# ATMEGA.net
KiCad netlist of a schematic drawn in EAGLE
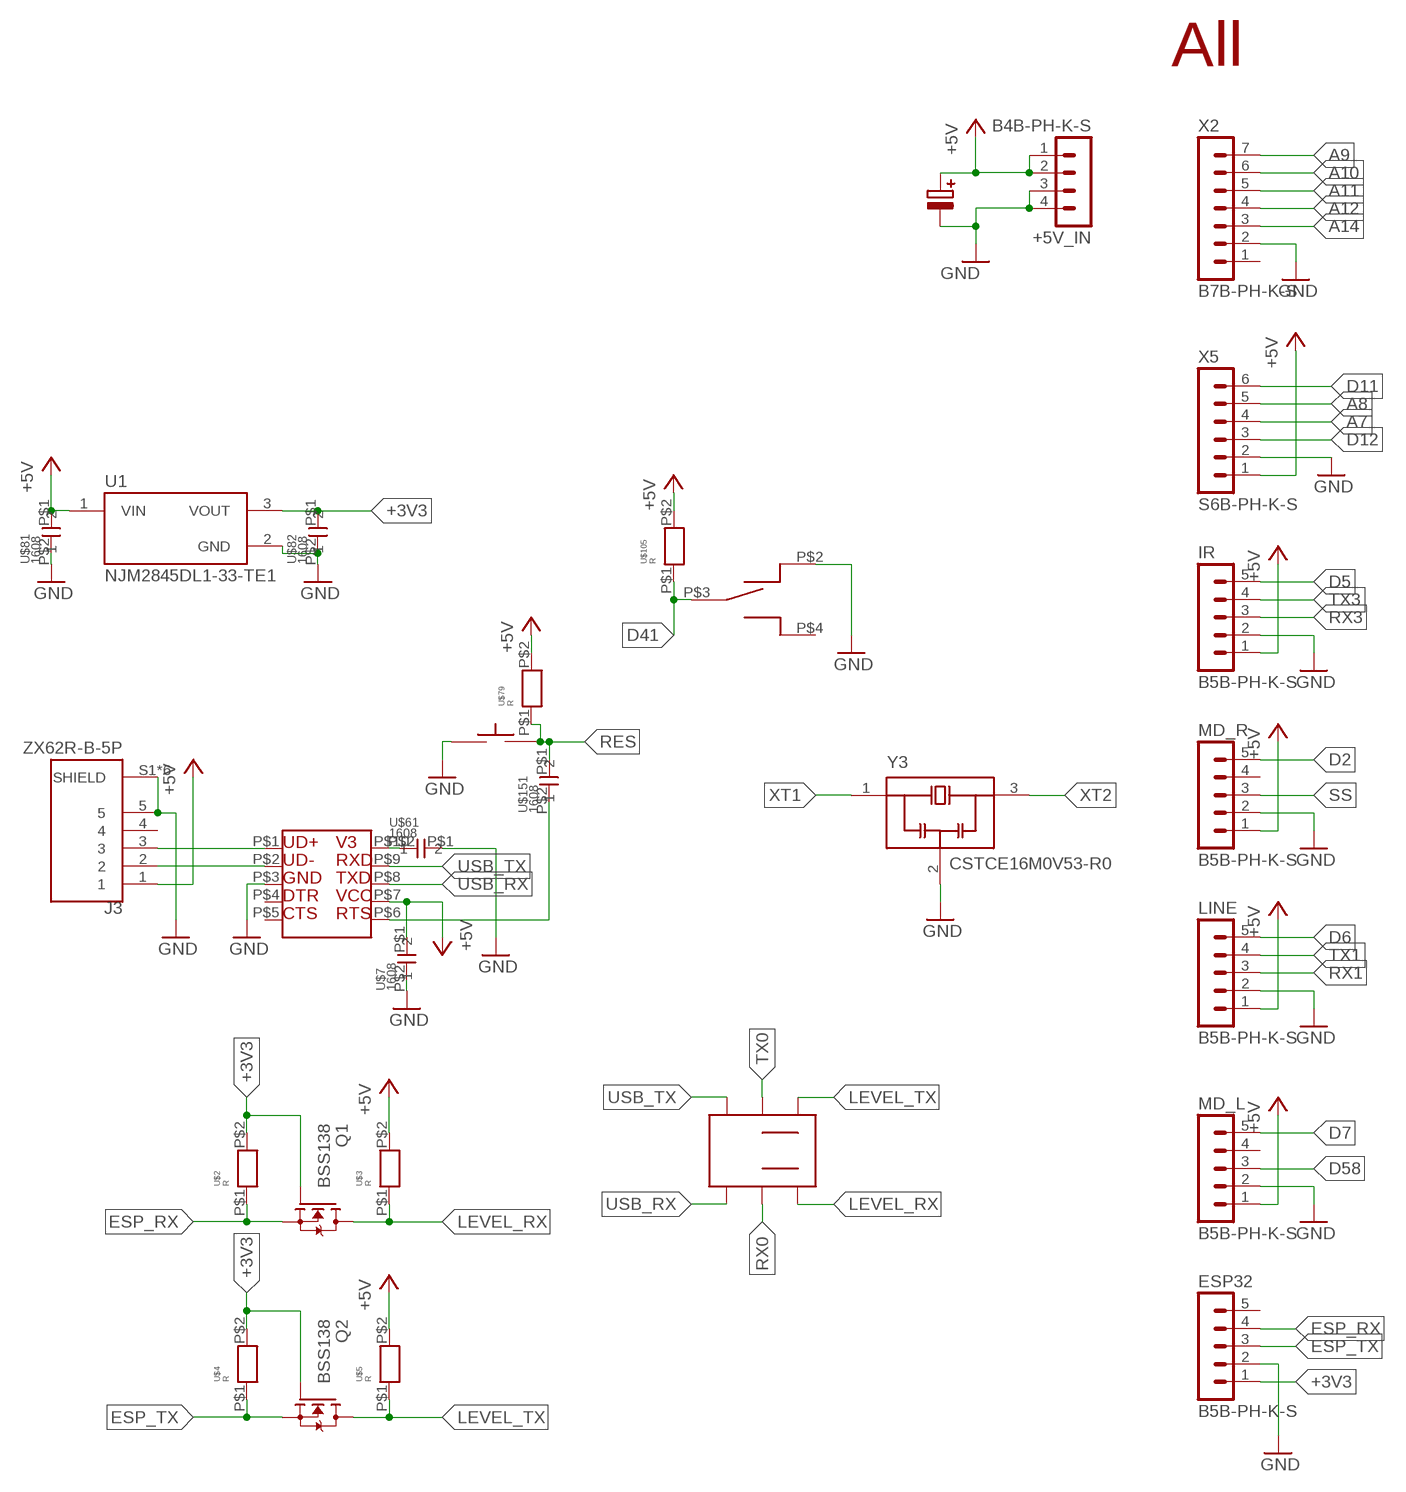
[diagram p0: schematic, sheet 1, part 1 of 2]
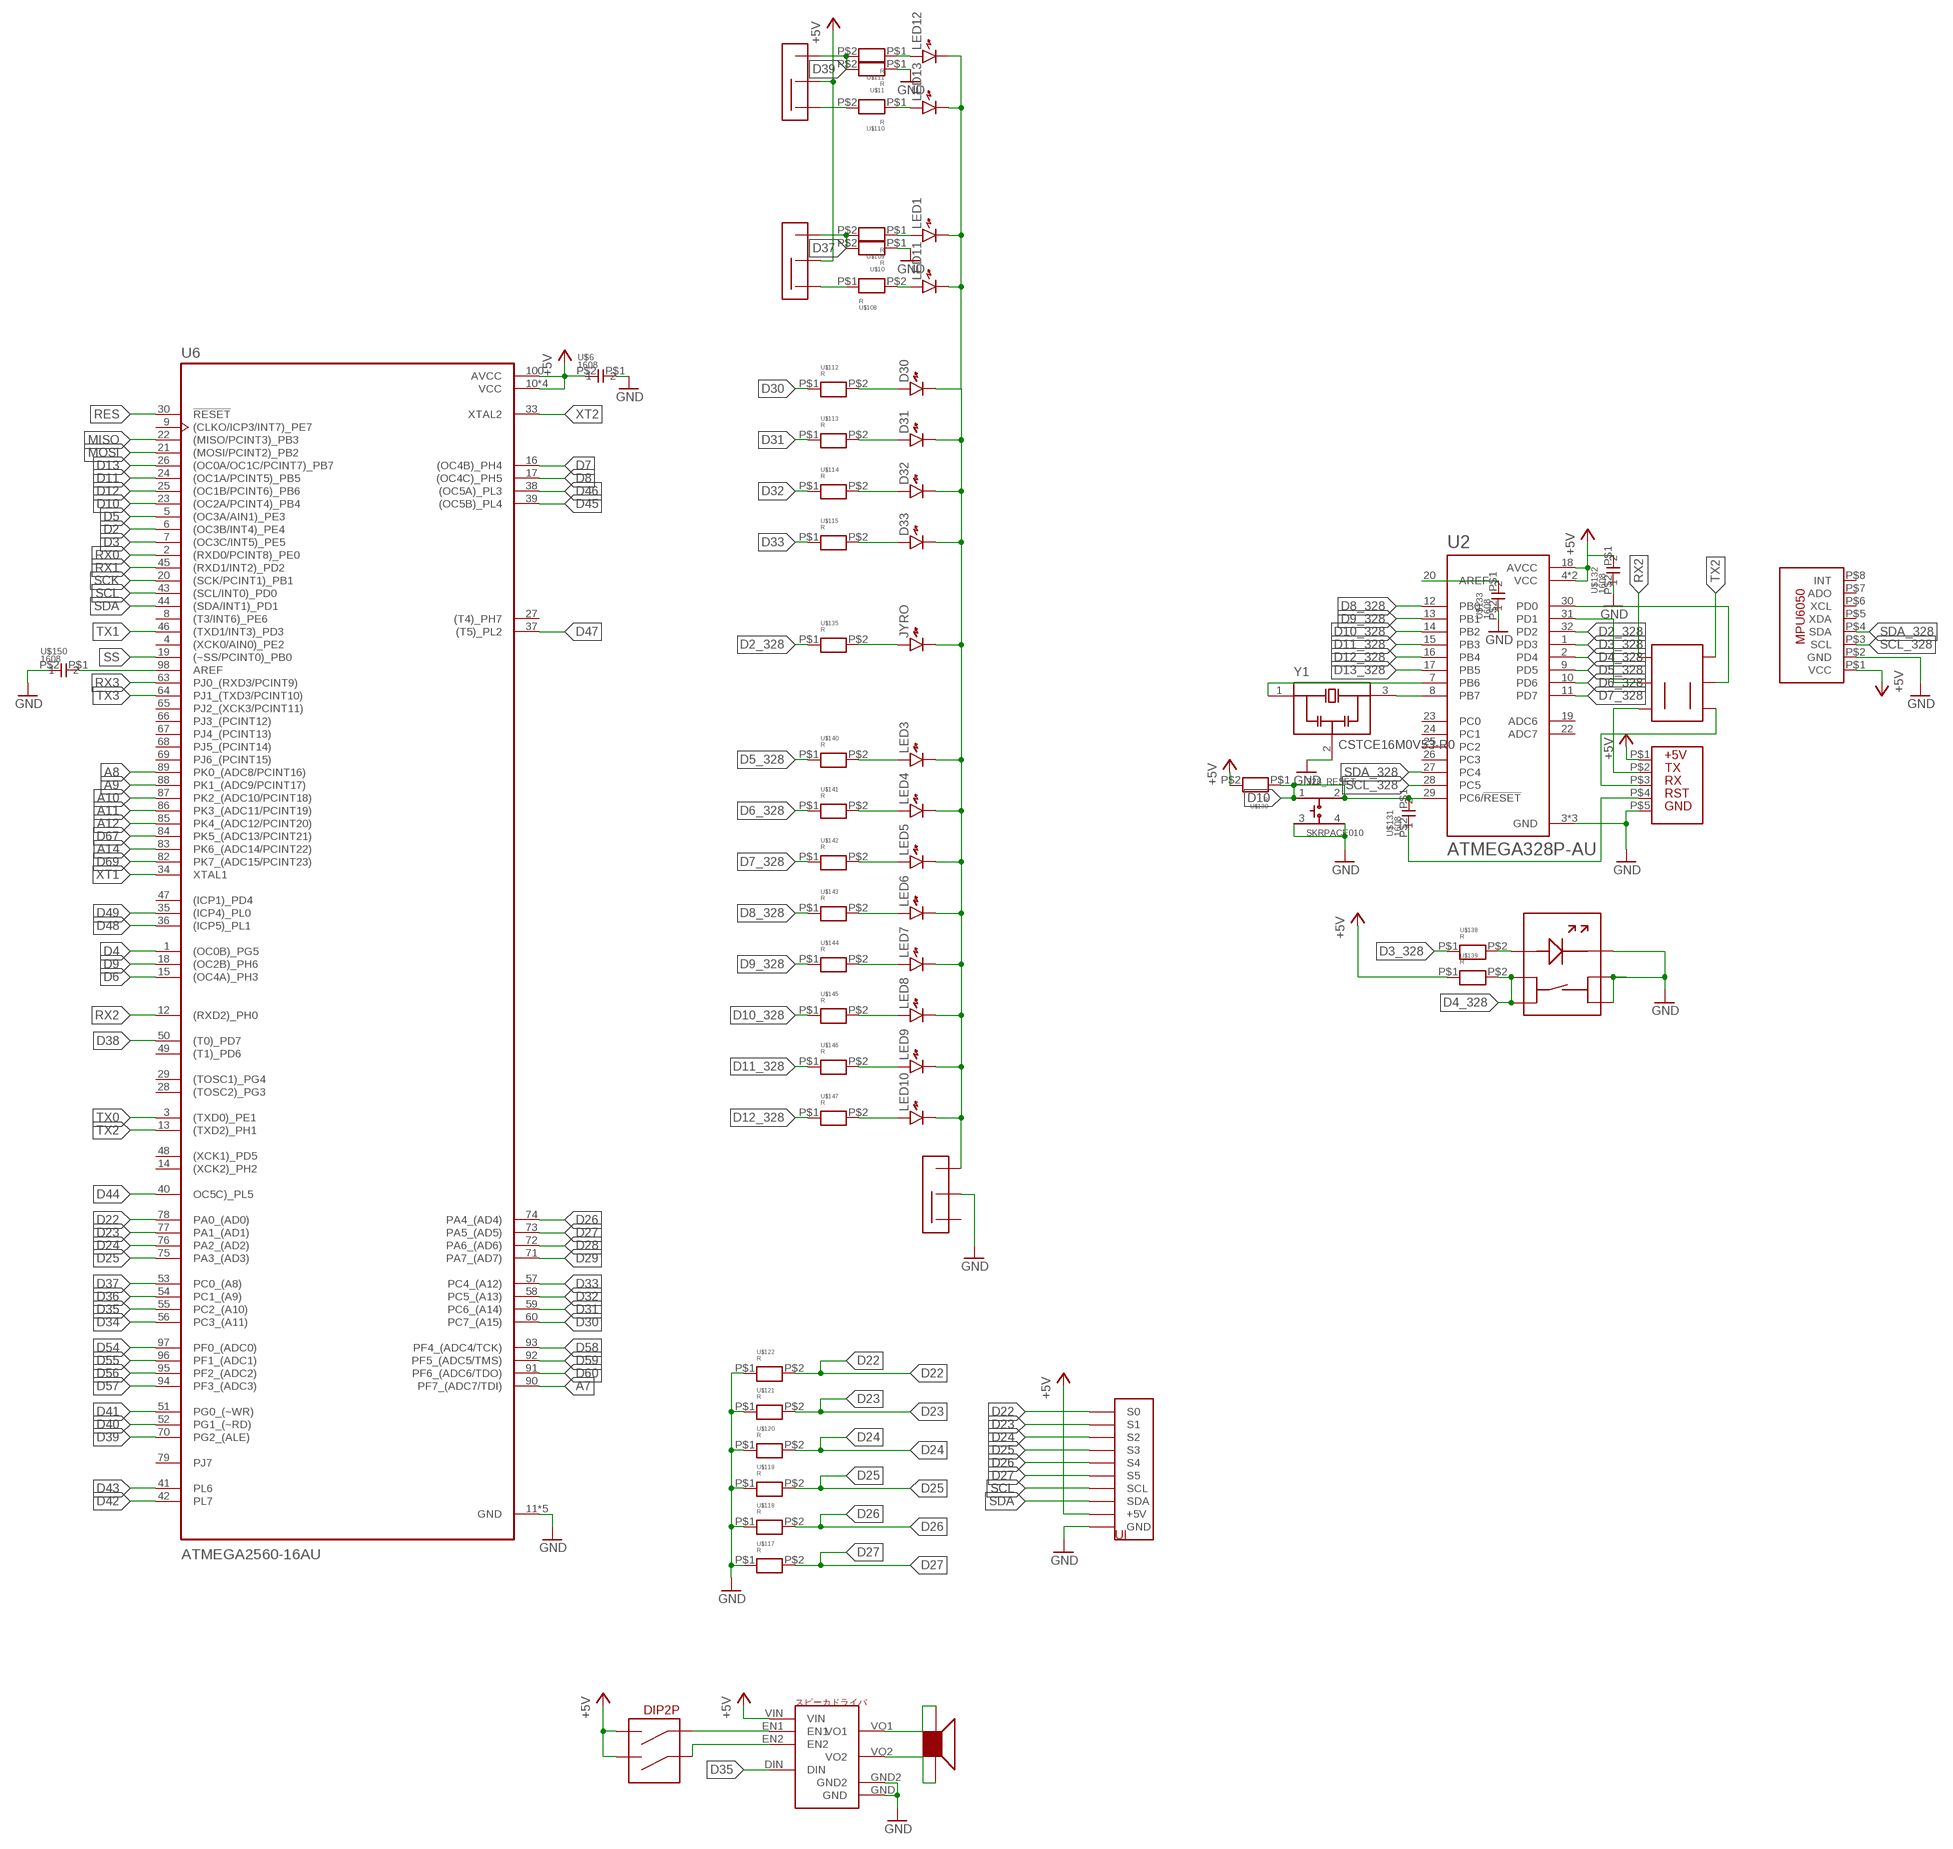
[diagram p1: schematic, sheet 1, part 2 of 2]

(export (version "E")
  (design (tool "Eeschema 10.0.6"))
  (components
    (comp (ref "+5V_IN")
      (value "B4B-PH-K-S")
      (footprint "eagle-import:B4B-PH-K-S")
      (libsource (lib "eagle-import") (part "B4B-PH-K-S"))
    )
    (comp (ref "328_RESET")
      (value "SKRPACE010")
      (footprint "eagle-import:SW_SKRPACE010")
      (fields (field (name "MF") "ALPS"))
      (libsource (lib "eagle-import") (part "SKRPACE010"))
    )
    (comp (ref "D30")
      (value "LED1608")
      (footprint "eagle-import:LED1608")
      (libsource (lib "eagle-import") (part "LED1608"))
    )
    (comp (ref "D31")
      (value "LED1608")
      (footprint "eagle-import:LED1608")
      (libsource (lib "eagle-import") (part "LED1608"))
    )
    (comp (ref "D32")
      (value "LED1608")
      (footprint "eagle-import:LED1608")
      (libsource (lib "eagle-import") (part "LED1608"))
    )
    (comp (ref "D33")
      (value "LED1608")
      (footprint "eagle-import:LED1608")
      (libsource (lib "eagle-import") (part "LED1608"))
    )
    (comp (ref "ESP32")
      (value "B5B-PH-K-S")
      (footprint "eagle-import:B5B-PH-K-S")
      (libsource (lib "eagle-import") (part "B5B-PH-K-S"))
    )
    (comp (ref "IR")
      (value "B5B-PH-K-S")
      (footprint "eagle-import:B5B-PH-K-S")
      (libsource (lib "eagle-import") (part "B5B-PH-K-S"))
    )
    (comp (ref "J3")
      (value "ZX62R-B-5P")
      (footprint "eagle-import:HRS_ZX62R-B-5P")
      (fields (field (name "MF") "Hirose"))
      (libsource (lib "eagle-import") (part "ZX62R-B-5P"))
    )
    (comp (ref "JYRO")
      (value "LED1608")
      (footprint "eagle-import:LED1608")
      (libsource (lib "eagle-import") (part "LED1608"))
    )
    (comp (ref "LED1")
      (value "LED1608")
      (footprint "eagle-import:LED1608")
      (libsource (lib "eagle-import") (part "LED1608"))
    )
    (comp (ref "LED3")
      (value "LED1608")
      (footprint "eagle-import:LED1608")
      (libsource (lib "eagle-import") (part "LED1608"))
    )
    (comp (ref "LED4")
      (value "LED1608")
      (footprint "eagle-import:LED1608")
      (libsource (lib "eagle-import") (part "LED1608"))
    )
    (comp (ref "LED5")
      (value "LED1608")
      (footprint "eagle-import:LED1608")
      (libsource (lib "eagle-import") (part "LED1608"))
    )
    (comp (ref "LED6")
      (value "LED1608")
      (footprint "eagle-import:LED1608")
      (libsource (lib "eagle-import") (part "LED1608"))
    )
    (comp (ref "LED7")
      (value "LED1608")
      (footprint "eagle-import:LED1608")
      (libsource (lib "eagle-import") (part "LED1608"))
    )
    (comp (ref "LED8")
      (value "LED1608")
      (footprint "eagle-import:LED1608")
      (libsource (lib "eagle-import") (part "LED1608"))
    )
    (comp (ref "LED9")
      (value "LED1608")
      (footprint "eagle-import:LED1608")
      (libsource (lib "eagle-import") (part "LED1608"))
    )
    (comp (ref "LED10")
      (value "LED1608")
      (footprint "eagle-import:LED1608")
      (libsource (lib "eagle-import") (part "LED1608"))
    )
    (comp (ref "LED11")
      (value "LED1608")
      (footprint "eagle-import:LED1608")
      (libsource (lib "eagle-import") (part "LED1608"))
    )
    (comp (ref "LED12")
      (value "LED1608")
      (footprint "eagle-import:LED1608")
      (libsource (lib "eagle-import") (part "LED1608"))
    )
    (comp (ref "LED13")
      (value "LED1608")
      (footprint "eagle-import:LED1608")
      (libsource (lib "eagle-import") (part "LED1608"))
    )
    (comp (ref "LINE")
      (value "B5B-PH-K-S")
      (footprint "eagle-import:B5B-PH-K-S")
      (libsource (lib "eagle-import") (part "B5B-PH-K-S"))
    )
    (comp (ref "MD_L")
      (value "B5B-PH-K-S")
      (footprint "eagle-import:B5B-PH-K-S")
      (libsource (lib "eagle-import") (part "B5B-PH-K-S"))
    )
    (comp (ref "MD_R")
      (value "B5B-PH-K-S")
      (footprint "eagle-import:B5B-PH-K-S")
      (libsource (lib "eagle-import") (part "B5B-PH-K-S"))
    )
    (comp (ref "Q1")
      (value "BSS138")
      (footprint "eagle-import:SOT23")
      (fields (field (name "MF") "Fairchild"))
      (libsource (lib "eagle-import") (part "BSS138"))
    )
    (comp (ref "Q2")
      (value "BSS138")
      (footprint "eagle-import:SOT23")
      (fields (field (name "MF") "Fairchild"))
      (libsource (lib "eagle-import") (part "BSS138"))
    )
    (comp (ref "U$1")
      (value "25V100")
      (footprint "eagle-import:25V100")
      (libsource (lib "eagle-import") (part "25V100"))
    )
    (comp (ref "U$2") (value "R") (footprint "eagle-import:1608") (libsource (lib "eagle-import") (part "R")))
    (comp (ref "U$3") (value "R") (footprint "eagle-import:1608") (libsource (lib "eagle-import") (part "R")))
    (comp (ref "U$4") (value "R") (footprint "eagle-import:1608") (libsource (lib "eagle-import") (part "R")))
    (comp (ref "U$5") (value "R") (footprint "eagle-import:1608") (libsource (lib "eagle-import") (part "R")))
    (comp (ref "U$6")
      (value "1608")
      (footprint "eagle-import:CON")
      (libsource (lib "eagle-import") (part "1608"))
    )
    (comp (ref "U$7")
      (value "1608")
      (footprint "eagle-import:CON")
      (libsource (lib "eagle-import") (part "1608"))
    )
    (comp (ref "U$8")
      (value "2SW")
      (footprint "eagle-import:2SW")
      (libsource (lib "eagle-import") (part "2SW"))
    )
    (comp (ref "U$9") (value "S") (footprint "eagle-import:S") (libsource (lib "eagle-import") (part "S")))
    (comp (ref "U$10")
      (value "R")
      (footprint "eagle-import:1608")
      (libsource (lib "eagle-import") (part "R"))
    )
    (comp (ref "U$11")
      (value "R")
      (footprint "eagle-import:1608")
      (libsource (lib "eagle-import") (part "R"))
    )
    (comp (ref "U$12")
      (value "BUZA-")
      (footprint "eagle-import:ぶざー")
      (libsource (lib "eagle-import") (part "BUZA-"))
    )
    (comp (ref "U$13")
      (value "BUZA_DR")
      (footprint "eagle-import:BUZA_DR")
      (libsource (lib "eagle-import") (part "BUZA_DR"))
    )
    (comp (ref "U$14")
      (value "DIP2")
      (footprint "eagle-import:DIP2")
      (libsource (lib "eagle-import") (part "DIP2"))
    )
    (comp (ref "U$46")
      (value "CH340K")
      (footprint "eagle-import:CH340K")
      (libsource (lib "eagle-import") (part "CH340K"))
    )
    (comp (ref "U$61")
      (value "1608")
      (footprint "eagle-import:CON")
      (libsource (lib "eagle-import") (part "1608"))
    )
    (comp (ref "U$79")
      (value "R")
      (footprint "eagle-import:1608")
      (libsource (lib "eagle-import") (part "R"))
    )
    (comp (ref "U$80")
      (value "TAKUTO")
      (footprint "eagle-import:12")
      (libsource (lib "eagle-import") (part "TAKUTO"))
    )
    (comp (ref "U$81")
      (value "1608")
      (footprint "eagle-import:CON")
      (libsource (lib "eagle-import") (part "1608"))
    )
    (comp (ref "U$82")
      (value "1608")
      (footprint "eagle-import:CON")
      (libsource (lib "eagle-import") (part "1608"))
    )
    (comp (ref "U$93")
      (value "ジャイロ")
      (footprint "eagle-import:ジャイロ")
      (libsource (lib "eagle-import") (part "ジャイロ"))
    )
    (comp (ref "U$105")
      (value "R")
      (footprint "eagle-import:1608")
      (libsource (lib "eagle-import") (part "R"))
    )
    (comp (ref "U$106")
      (value "SSW")
      (footprint "eagle-import:SSW")
      (libsource (lib "eagle-import") (part "SSW"))
    )
    (comp (ref "U$107")
      (value "SSW")
      (footprint "eagle-import:SSW")
      (libsource (lib "eagle-import") (part "SSW"))
    )
    (comp (ref "U$108")
      (value "R")
      (footprint "eagle-import:1608")
      (libsource (lib "eagle-import") (part "R"))
    )
    (comp (ref "U$109")
      (value "R")
      (footprint "eagle-import:1608")
      (libsource (lib "eagle-import") (part "R"))
    )
    (comp (ref "U$110")
      (value "R")
      (footprint "eagle-import:1608")
      (libsource (lib "eagle-import") (part "R"))
    )
    (comp (ref "U$111")
      (value "R")
      (footprint "eagle-import:1608")
      (libsource (lib "eagle-import") (part "R"))
    )
    (comp (ref "U$112")
      (value "R")
      (footprint "eagle-import:1608")
      (libsource (lib "eagle-import") (part "R"))
    )
    (comp (ref "U$113")
      (value "R")
      (footprint "eagle-import:1608")
      (libsource (lib "eagle-import") (part "R"))
    )
    (comp (ref "U$114")
      (value "R")
      (footprint "eagle-import:1608")
      (libsource (lib "eagle-import") (part "R"))
    )
    (comp (ref "U$115")
      (value "R")
      (footprint "eagle-import:1608")
      (libsource (lib "eagle-import") (part "R"))
    )
    (comp (ref "U$117")
      (value "R")
      (footprint "eagle-import:1608")
      (libsource (lib "eagle-import") (part "R"))
    )
    (comp (ref "U$118")
      (value "R")
      (footprint "eagle-import:1608")
      (libsource (lib "eagle-import") (part "R"))
    )
    (comp (ref "U$119")
      (value "R")
      (footprint "eagle-import:1608")
      (libsource (lib "eagle-import") (part "R"))
    )
    (comp (ref "U$120")
      (value "R")
      (footprint "eagle-import:1608")
      (libsource (lib "eagle-import") (part "R"))
    )
    (comp (ref "U$121")
      (value "R")
      (footprint "eagle-import:1608")
      (libsource (lib "eagle-import") (part "R"))
    )
    (comp (ref "U$122")
      (value "R")
      (footprint "eagle-import:1608")
      (libsource (lib "eagle-import") (part "R"))
    )
    (comp (ref "U$130")
      (value "R")
      (footprint "eagle-import:1608")
      (libsource (lib "eagle-import") (part "R"))
    )
    (comp (ref "U$131")
      (value "1608")
      (footprint "eagle-import:CON")
      (libsource (lib "eagle-import") (part "1608"))
    )
    (comp (ref "U$132")
      (value "1608")
      (footprint "eagle-import:CON")
      (libsource (lib "eagle-import") (part "1608"))
    )
    (comp (ref "U$133")
      (value "1608")
      (footprint "eagle-import:CON")
      (libsource (lib "eagle-import") (part "1608"))
    )
    (comp (ref "U$134")
      (value "SI")
      (footprint "eagle-import:SI")
      (libsource (lib "eagle-import") (part "SI"))
    )
    (comp (ref "U$135")
      (value "R")
      (footprint "eagle-import:1608")
      (libsource (lib "eagle-import") (part "R"))
    )
    (comp (ref "U$136")
      (value "2SW")
      (footprint "eagle-import:2SW")
      (libsource (lib "eagle-import") (part "2SW"))
    )
    (comp (ref "U$137")
      (value "SWLED")
      (footprint "eagle-import:SWLED")
      (libsource (lib "eagle-import") (part "SWLED"))
    )
    (comp (ref "U$138")
      (value "R")
      (footprint "eagle-import:1608")
      (libsource (lib "eagle-import") (part "R"))
    )
    (comp (ref "U$139")
      (value "R")
      (footprint "eagle-import:1608")
      (libsource (lib "eagle-import") (part "R"))
    )
    (comp (ref "U$140")
      (value "R")
      (footprint "eagle-import:1608")
      (libsource (lib "eagle-import") (part "R"))
    )
    (comp (ref "U$141")
      (value "R")
      (footprint "eagle-import:1608")
      (libsource (lib "eagle-import") (part "R"))
    )
    (comp (ref "U$142")
      (value "R")
      (footprint "eagle-import:1608")
      (libsource (lib "eagle-import") (part "R"))
    )
    (comp (ref "U$143")
      (value "R")
      (footprint "eagle-import:1608")
      (libsource (lib "eagle-import") (part "R"))
    )
    (comp (ref "U$144")
      (value "R")
      (footprint "eagle-import:1608")
      (libsource (lib "eagle-import") (part "R"))
    )
    (comp (ref "U$145")
      (value "R")
      (footprint "eagle-import:1608")
      (libsource (lib "eagle-import") (part "R"))
    )
    (comp (ref "U$146")
      (value "R")
      (footprint "eagle-import:1608")
      (libsource (lib "eagle-import") (part "R"))
    )
    (comp (ref "U$147")
      (value "R")
      (footprint "eagle-import:1608")
      (libsource (lib "eagle-import") (part "R"))
    )
    (comp (ref "U$148")
      (value "SSW")
      (footprint "eagle-import:SSW")
      (libsource (lib "eagle-import") (part "SSW"))
    )
    (comp (ref "U$149")
      (value "UI")
      (footprint "eagle-import:UI")
      (libsource (lib "eagle-import") (part "UI"))
    )
    (comp (ref "U$150")
      (value "1608")
      (footprint "eagle-import:CON")
      (libsource (lib "eagle-import") (part "1608"))
    )
    (comp (ref "U$151")
      (value "1608")
      (footprint "eagle-import:CON")
      (libsource (lib "eagle-import") (part "1608"))
    )
    (comp (ref "U$152")
      (value "ALL")
      (footprint "eagle-import:ALL")
      (libsource (lib "eagle-import") (part "ALL"))
    )
    (comp (ref "U1")
      (value "NJM2845DL1-33-TE1")
      (footprint "eagle-import:DPAK228P968X238-4N")
      (fields (field (name "MF") "NJR Corporation/NJRC"))
      (libsource (lib "eagle-import") (part "NJM2845DL1-33-TE1"))
    )
    (comp (ref "U2")
      (value "ATMEGA328P-AU")
      (footprint "eagle-import:QFP80P900X900X120-32N")
      (fields (field (name "MF") "Microchip Technology"))
      (libsource (lib "eagle-import") (part "ATMEGA328P-AU"))
    )
    (comp (ref "U6")
      (value "ATMEGA2560-16AU")
      (footprint "eagle-import:QFP50P1600X1600X120-100N")
      (fields (field (name "MF") "Microchip Technology"))
      (libsource (lib "eagle-import") (part "ATMEGA2560-16AU"))
    )
    (comp (ref "X2")
      (value "B7B-PH-K-S")
      (footprint "eagle-import:B7B-PH-K-S")
      (libsource (lib "eagle-import") (part "B7B-PH-K-S"))
    )
    (comp (ref "X5")
      (value "S6B-PH-K-S")
      (footprint "eagle-import:S6B-PH-K-S")
      (libsource (lib "eagle-import") (part "S6B-PH-K-S"))
    )
    (comp (ref "Y1")
      (value "CSTCE16M0V53-R0")
      (footprint "eagle-import:OSC_CSTCE16M0V53-R0")
      (fields (field (name "MANUFACTURER") "Murata"))
      (libsource (lib "eagle-import") (part "CSTCE16M0V53-R0"))
    )
    (comp (ref "Y3")
      (value "CSTCE16M0V53-R0")
      (footprint "eagle-import:OSC_CSTCE16M0V53-R0")
      (fields (field (name "MANUFACTURER") "Murata"))
      (libsource (lib "eagle-import") (part "CSTCE16M0V53-R0"))
    )
  )
  (nets
    (net (code "1") (name "+3V3") (class "Default")
      (node (ref "ESP32") (pin "1") (pinfunction "1_1") (pintype "passive"))
      (node (ref "Q1") (pin "1") (pinfunction "G_1") (pintype "passive"))
      (node (ref "Q2") (pin "1") (pinfunction "G_1") (pintype "passive"))
      (node (ref "U$2") (pin "P$2") (pinfunction "P$2_P$2") (pintype "bidirectional"))
      (node (ref "U$4") (pin "P$2") (pinfunction "P$2_P$2") (pintype "bidirectional"))
      (node (ref "U$82") (pin "P$1") (pinfunction "1_P$1") (pintype "bidirectional"))
      (node (ref "U1") (pin "3") (pinfunction "VOUT_3") (pintype "output"))
    )
    (net (code "2") (name "+5V") (class "Default")
      (node (ref "+5V_IN") (pin "1") (pinfunction "1_1") (pintype "passive"))
      (node (ref "+5V_IN") (pin "2") (pinfunction "2_2") (pintype "passive"))
      (node (ref "IR") (pin "1") (pinfunction "1_1") (pintype "passive"))
      (node (ref "J3") (pin "1") (pinfunction "1_1") (pintype "passive"))
      (node (ref "LINE") (pin "1") (pinfunction "1_1") (pintype "passive"))
      (node (ref "MD_L") (pin "1") (pinfunction "1_1") (pintype "passive"))
      (node (ref "MD_R") (pin "1") (pinfunction "1_1") (pintype "passive"))
      (node (ref "U$1") (pin "P$1") (pinfunction "P$1_P$1") (pintype "bidirectional"))
      (node (ref "U$105") (pin "P$2") (pinfunction "P$2_P$2") (pintype "bidirectional"))
      (node (ref "U$106") (pin "P$3") (pinfunction "P$2_P$3") (pintype "bidirectional"))
      (node (ref "U$107") (pin "P$3") (pinfunction "P$2_P$3") (pintype "bidirectional"))
      (node (ref "U$13") (pin "VIN") (pinfunction "VIN_VIN") (pintype "bidirectional"))
      (node (ref "U$130") (pin "P$2") (pinfunction "P$2_P$2") (pintype "bidirectional"))
      (node (ref "U$132") (pin "P$1") (pinfunction "1_P$1") (pintype "bidirectional"))
      (node (ref "U$134") (pin "P$1") (pinfunction "P$1_P$1") (pintype "bidirectional"))
      (node (ref "U$139") (pin "P$1") (pinfunction "P$1_P$1") (pintype "bidirectional"))
      (node (ref "U$14") (pin "P$15") (pinfunction "P$15_P$15") (pintype "bidirectional"))
      (node (ref "U$14") (pin "P$16") (pinfunction "P$16_P$16") (pintype "bidirectional"))
      (node (ref "U$149") (pin "P$1") (pinfunction "+5V_P$1") (pintype "bidirectional"))
      (node (ref "U$3") (pin "P$2") (pinfunction "P$2_P$2") (pintype "bidirectional"))
      (node (ref "U$46") (pin "P$7") (pinfunction "P$7_P$7") (pintype "bidirectional"))
      (node (ref "U$5") (pin "P$2") (pinfunction "P$2_P$2") (pintype "bidirectional"))
      (node (ref "U$6") (pin "P$2") (pinfunction "2_P$2") (pintype "bidirectional"))
      (node (ref "U$7") (pin "P$1") (pinfunction "1_P$1") (pintype "bidirectional"))
      (node (ref "U$79") (pin "P$2") (pinfunction "P$2_P$2") (pintype "bidirectional"))
      (node (ref "U$81") (pin "P$1") (pinfunction "1_P$1") (pintype "bidirectional"))
      (node (ref "U$93") (pin "P$1") (pinfunction "VCC_P$1") (pintype "bidirectional"))
      (node (ref "U1") (pin "1") (pinfunction "VIN_1") (pintype "input"))
      (node (ref "U2") (pin "18") (pinfunction "AVCC_18") (pintype "power_in"))
      (node (ref "U2") (pin "4") (pinfunction "VCC_4") (pintype "power_in"))
      (node (ref "U2") (pin "6") (pinfunction "VCC_6") (pintype "power_in"))
      (node (ref "U6") (pin "10") (pinfunction "VCC_10") (pintype "power_in"))
      (node (ref "U6") (pin "100") (pinfunction "AVCC_100") (pintype "power_in"))
      (node (ref "U6") (pin "31") (pinfunction "VCC_31") (pintype "power_in"))
      (node (ref "U6") (pin "61") (pinfunction "VCC_61") (pintype "power_in"))
      (node (ref "U6") (pin "80") (pinfunction "VCC_80") (pintype "power_in"))
      (node (ref "X5") (pin "1") (pinfunction "1_1") (pintype "passive"))
    )
    (net (code "3") (name "A7") (class "Default")
      (node (ref "U6") (pin "90") (pinfunction "PF7_(ADC7/TDI)_90") (pintype "bidirectional"))
      (node (ref "X5") (pin "4") (pinfunction "4_4") (pintype "passive"))
    )
    (net (code "4") (name "A8") (class "Default")
      (node (ref "U6") (pin "89") (pinfunction "PK0_(ADC8/PCINT16)_89") (pintype "input"))
      (node (ref "X5") (pin "5") (pinfunction "5_5") (pintype "passive"))
    )
    (net (code "5") (name "A9") (class "Default")
      (node (ref "U6") (pin "88") (pinfunction "PK1_(ADC9/PCINT17)_88") (pintype "input"))
      (node (ref "X2") (pin "7") (pinfunction "7_7") (pintype "passive"))
    )
    (net (code "6") (name "A10") (class "Default")
      (node (ref "U6") (pin "87") (pinfunction "PK2_(ADC10/PCINT18)_87") (pintype "input"))
      (node (ref "X2") (pin "6") (pinfunction "6_6") (pintype "passive"))
    )
    (net (code "7") (name "A11") (class "Default")
      (node (ref "U6") (pin "86") (pinfunction "PK3_(ADC11/PCINT19)_86") (pintype "input"))
      (node (ref "X2") (pin "5") (pinfunction "5_5") (pintype "passive"))
    )
    (net (code "8") (name "A12") (class "Default")
      (node (ref "U6") (pin "85") (pinfunction "PK4_(ADC12/PCINT20)_85") (pintype "input"))
      (node (ref "X2") (pin "4") (pinfunction "4_4") (pintype "passive"))
    )
    (net (code "9") (name "A14") (class "Default")
      (node (ref "U6") (pin "83") (pinfunction "PK6_(ADC14/PCINT22)_83") (pintype "input"))
      (node (ref "X2") (pin "3") (pinfunction "3_3") (pintype "passive"))
    )
    (net (code "10") (name "D2") (class "Default")
      (node (ref "MD_R") (pin "5") (pinfunction "5_5") (pintype "passive"))
      (node (ref "U6") (pin "6") (pinfunction "(OC3B/INT4)_PE4_6") (pintype "input"))
    )
    (net (code "11") (name "D2_328") (class "Default")
      (node (ref "U$135") (pin "P$1") (pinfunction "P$1_P$1") (pintype "bidirectional"))
      (node (ref "U2") (pin "32") (pinfunction "PD2_32") (pintype "bidirectional"))
    )
    (net (code "12") (name "D3") (class "Default")
      (node (ref "U6") (pin "7") (pinfunction "(OC3C/INT5)_PE5_7") (pintype "input"))
    )
    (net (code "13") (name "D3_328") (class "Default")
      (node (ref "U$138") (pin "P$1") (pinfunction "P$1_P$1") (pintype "bidirectional"))
      (node (ref "U2") (pin "1") (pinfunction "PD3_1") (pintype "bidirectional"))
    )
    (net (code "14") (name "D4") (class "Default")
      (node (ref "U6") (pin "1") (pinfunction "(OC0B)_PG5_1") (pintype "bidirectional"))
    )
    (net (code "15") (name "D4_328") (class "Default")
      (node (ref "U$137") (pin "1") (pinfunction "1_1") (pintype "bidirectional"))
      (node (ref "U$137") (pin "2") (pinfunction "2_2") (pintype "bidirectional"))
      (node (ref "U$139") (pin "P$2") (pinfunction "P$2_P$2") (pintype "bidirectional"))
      (node (ref "U2") (pin "2") (pinfunction "PD4_2") (pintype "bidirectional"))
    )
    (net (code "16") (name "D5") (class "Default")
      (node (ref "IR") (pin "5") (pinfunction "5_5") (pintype "passive"))
      (node (ref "U6") (pin "5") (pinfunction "(OC3A/AIN1)_PE3_5") (pintype "input"))
    )
    (net (code "17") (name "D5_328") (class "Default")
      (node (ref "U$140") (pin "P$1") (pinfunction "P$1_P$1") (pintype "bidirectional"))
      (node (ref "U2") (pin "9") (pinfunction "PD5_9") (pintype "bidirectional"))
    )
    (net (code "18") (name "D6") (class "Default")
      (node (ref "LINE") (pin "5") (pinfunction "5_5") (pintype "passive"))
      (node (ref "U6") (pin "15") (pinfunction "(OC4A)_PH3_15") (pintype "bidirectional"))
    )
    (net (code "19") (name "D6_328") (class "Default")
      (node (ref "U$141") (pin "P$1") (pinfunction "P$1_P$1") (pintype "bidirectional"))
      (node (ref "U2") (pin "10") (pinfunction "PD6_10") (pintype "bidirectional"))
    )
    (net (code "20") (name "D7") (class "Default")
      (node (ref "MD_L") (pin "5") (pinfunction "5_5") (pintype "passive"))
      (node (ref "U6") (pin "16") (pinfunction "(OC4B)_PH4_16") (pintype "bidirectional"))
    )
    (net (code "21") (name "D7_328") (class "Default")
      (node (ref "U$142") (pin "P$1") (pinfunction "P$1_P$1") (pintype "bidirectional"))
      (node (ref "U2") (pin "11") (pinfunction "PD7_11") (pintype "bidirectional"))
    )
    (net (code "22") (name "D8") (class "Default")
      (node (ref "U6") (pin "17") (pinfunction "(OC4C)_PH5_17") (pintype "bidirectional"))
    )
    (net (code "23") (name "D8_328") (class "Default")
      (node (ref "U$143") (pin "P$1") (pinfunction "P$1_P$1") (pintype "bidirectional"))
      (node (ref "U2") (pin "12") (pinfunction "PB0_12") (pintype "bidirectional"))
    )
    (net (code "24") (name "D9") (class "Default")
      (node (ref "U6") (pin "18") (pinfunction "(OC2B)_PH6_18") (pintype "bidirectional"))
    )
    (net (code "25") (name "D9_328") (class "Default")
      (node (ref "U$144") (pin "P$1") (pinfunction "P$1_P$1") (pintype "bidirectional"))
      (node (ref "U2") (pin "13") (pinfunction "PB1_13") (pintype "bidirectional"))
    )
    (net (code "26") (name "D10") (class "Default")
      (node (ref "328_RESET") (pin "1") (pinfunction "1_1") (pintype "bidirectional"))
      (node (ref "328_RESET") (pin "2") (pinfunction "2_2") (pintype "bidirectional"))
      (node (ref "U$130") (pin "P$1") (pinfunction "P$1_P$1") (pintype "bidirectional"))
      (node (ref "U$131") (pin "P$1") (pinfunction "1_P$1") (pintype "bidirectional"))
      (node (ref "U2") (pin "29") (pinfunction "PC6/~{RESET}_29") (pintype "bidirectional"))
      (node (ref "U6") (pin "23") (pinfunction "(OC2A/PCINT4)_PB4_23") (pintype "input"))
    )
    (net (code "27") (name "D10_328") (class "Default")
      (node (ref "U$145") (pin "P$1") (pinfunction "P$1_P$1") (pintype "bidirectional"))
      (node (ref "U2") (pin "14") (pinfunction "PB2_14") (pintype "bidirectional"))
    )
    (net (code "28") (name "D11") (class "Default")
      (node (ref "U6") (pin "24") (pinfunction "(OC1A/PCINT5)_PB5_24") (pintype "input"))
      (node (ref "X5") (pin "6") (pinfunction "6_6") (pintype "passive"))
    )
    (net (code "29") (name "D11_328") (class "Default")
      (node (ref "U$146") (pin "P$1") (pinfunction "P$1_P$1") (pintype "bidirectional"))
      (node (ref "U2") (pin "15") (pinfunction "PB3_15") (pintype "bidirectional"))
    )
    (net (code "30") (name "D12") (class "Default")
      (node (ref "U6") (pin "25") (pinfunction "(OC1B/PCINT6)_PB6_25") (pintype "input"))
      (node (ref "X5") (pin "3") (pinfunction "3_3") (pintype "passive"))
    )
    (net (code "31") (name "D12_328") (class "Default")
      (node (ref "U$147") (pin "P$1") (pinfunction "P$1_P$1") (pintype "bidirectional"))
      (node (ref "U2") (pin "16") (pinfunction "PB4_16") (pintype "bidirectional"))
    )
    (net (code "32") (name "D13") (class "Default")
      (node (ref "U6") (pin "26") (pinfunction "(OC0A/OC1C/PCINT7)_PB7_26") (pintype "input"))
    )
    (net (code "33") (name "D13_328") (class "Default")
      (node (ref "U2") (pin "17") (pinfunction "PB5_17") (pintype "bidirectional"))
    )
    (net (code "34") (name "D22") (class "Default")
      (node (ref "U$122") (pin "P$2") (pinfunction "P$2_P$2") (pintype "bidirectional"))
      (node (ref "U$149") (pin "P$3") (pinfunction "S0_P$3") (pintype "bidirectional"))
      (node (ref "U6") (pin "78") (pinfunction "PA0_(AD0)_78") (pintype "bidirectional"))
    )
    (net (code "35") (name "D23") (class "Default")
      (node (ref "U$121") (pin "P$2") (pinfunction "P$2_P$2") (pintype "bidirectional"))
      (node (ref "U$149") (pin "P$4") (pinfunction "S1_P$4") (pintype "bidirectional"))
      (node (ref "U6") (pin "77") (pinfunction "PA1_(AD1)_77") (pintype "bidirectional"))
    )
    (net (code "36") (name "D24") (class "Default")
      (node (ref "U$120") (pin "P$2") (pinfunction "P$2_P$2") (pintype "bidirectional"))
      (node (ref "U$149") (pin "P$5") (pinfunction "S2_P$5") (pintype "bidirectional"))
      (node (ref "U6") (pin "76") (pinfunction "PA2_(AD2)_76") (pintype "bidirectional"))
    )
    (net (code "37") (name "D25") (class "Default")
      (node (ref "U$119") (pin "P$2") (pinfunction "P$2_P$2") (pintype "bidirectional"))
      (node (ref "U$149") (pin "P$6") (pinfunction "S3_P$6") (pintype "bidirectional"))
      (node (ref "U6") (pin "75") (pinfunction "PA3_(AD3)_75") (pintype "bidirectional"))
    )
    (net (code "38") (name "D26") (class "Default")
      (node (ref "U$118") (pin "P$2") (pinfunction "P$2_P$2") (pintype "bidirectional"))
      (node (ref "U$149") (pin "P$7") (pinfunction "S4_P$7") (pintype "bidirectional"))
      (node (ref "U6") (pin "74") (pinfunction "PA4_(AD4)_74") (pintype "bidirectional"))
    )
    (net (code "39") (name "D27") (class "Default")
      (node (ref "U$117") (pin "P$2") (pinfunction "P$2_P$2") (pintype "bidirectional"))
      (node (ref "U$149") (pin "P$8") (pinfunction "S5_P$8") (pintype "bidirectional"))
      (node (ref "U6") (pin "73") (pinfunction "PA5_(AD5)_73") (pintype "bidirectional"))
    )
    (net (code "40") (name "D28") (class "Default")
      (node (ref "U6") (pin "72") (pinfunction "PA6_(AD6)_72") (pintype "bidirectional"))
    )
    (net (code "41") (name "D29") (class "Default")
      (node (ref "U6") (pin "71") (pinfunction "PA7_(AD7)_71") (pintype "bidirectional"))
    )
    (net (code "42") (name "D30") (class "Default")
      (node (ref "U$112") (pin "P$1") (pinfunction "P$1_P$1") (pintype "bidirectional"))
      (node (ref "U6") (pin "60") (pinfunction "PC7_(A15)_60") (pintype "bidirectional"))
    )
    (net (code "43") (name "D31") (class "Default")
      (node (ref "U$113") (pin "P$1") (pinfunction "P$1_P$1") (pintype "bidirectional"))
      (node (ref "U6") (pin "59") (pinfunction "PC6_(A14)_59") (pintype "bidirectional"))
    )
    (net (code "44") (name "D32") (class "Default")
      (node (ref "U$114") (pin "P$1") (pinfunction "P$1_P$1") (pintype "bidirectional"))
      (node (ref "U6") (pin "58") (pinfunction "PC5_(A13)_58") (pintype "bidirectional"))
    )
    (net (code "45") (name "D33") (class "Default")
      (node (ref "U$115") (pin "P$1") (pinfunction "P$1_P$1") (pintype "bidirectional"))
      (node (ref "U6") (pin "57") (pinfunction "PC4_(A12)_57") (pintype "bidirectional"))
    )
    (net (code "46") (name "D34") (class "Default")
      (node (ref "U6") (pin "56") (pinfunction "PC3_(A11)_56") (pintype "bidirectional"))
    )
    (net (code "47") (name "D35") (class "Default")
      (node (ref "U$13") (pin "DIN") (pinfunction "DIN_DIN") (pintype "bidirectional"))
      (node (ref "U6") (pin "55") (pinfunction "PC2_(A10)_55") (pintype "bidirectional"))
    )
    (net (code "48") (name "D36") (class "Default")
      (node (ref "U6") (pin "54") (pinfunction "PC1_(A9)_54") (pintype "bidirectional"))
    )
    (net (code "49") (name "D37") (class "Default")
      (node (ref "U$10") (pin "P$2") (pinfunction "P$2_P$2") (pintype "bidirectional"))
      (node (ref "U$106") (pin "P$2") (pinfunction "P$3_P$2") (pintype "bidirectional"))
      (node (ref "U$109") (pin "P$2") (pinfunction "P$2_P$2") (pintype "bidirectional"))
      (node (ref "U6") (pin "53") (pinfunction "PC0_(A8)_53") (pintype "bidirectional"))
    )
    (net (code "50") (name "D38") (class "Default")
      (node (ref "U6") (pin "50") (pinfunction "(T0)_PD7_50") (pintype "bidirectional"))
    )
    (net (code "51") (name "D39") (class "Default")
      (node (ref "U$107") (pin "P$2") (pinfunction "P$3_P$2") (pintype "bidirectional"))
      (node (ref "U$11") (pin "P$2") (pinfunction "P$2_P$2") (pintype "bidirectional"))
      (node (ref "U$111") (pin "P$2") (pinfunction "P$2_P$2") (pintype "bidirectional"))
      (node (ref "U6") (pin "70") (pinfunction "PG2_(ALE)_70") (pintype "bidirectional"))
    )
    (net (code "52") (name "D40") (class "Default")
      (node (ref "U6") (pin "52") (pinfunction "PG1_(~{RD})_52") (pintype "bidirectional"))
    )
    (net (code "53") (name "D41") (class "Default")
      (node (ref "U$105") (pin "P$1") (pinfunction "P$1_P$1") (pintype "bidirectional"))
      (node (ref "U$9") (pin "P$3") (pinfunction "2_P$3") (pintype "bidirectional"))
      (node (ref "U6") (pin "51") (pinfunction "PG0_(~{WR})_51") (pintype "bidirectional"))
    )
    (net (code "54") (name "D42") (class "Default")
      (node (ref "U6") (pin "42") (pinfunction "PL7_42") (pintype "bidirectional"))
    )
    (net (code "55") (name "D43") (class "Default")
      (node (ref "U6") (pin "41") (pinfunction "PL6_41") (pintype "bidirectional"))
    )
    (net (code "56") (name "D44") (class "Default")
      (node (ref "U6") (pin "40") (pinfunction "OC5C)_PL5_40") (pintype "bidirectional"))
    )
    (net (code "57") (name "D45") (class "Default")
      (node (ref "U6") (pin "39") (pinfunction "(OC5B)_PL4_39") (pintype "bidirectional"))
    )
    (net (code "58") (name "D46") (class "Default")
      (node (ref "U6") (pin "38") (pinfunction "(OC5A)_PL3_38") (pintype "bidirectional"))
    )
    (net (code "59") (name "D47") (class "Default")
      (node (ref "U6") (pin "37") (pinfunction "(T5)_PL2_37") (pintype "bidirectional"))
    )
    (net (code "60") (name "D48") (class "Default")
      (node (ref "U6") (pin "36") (pinfunction "(ICP5)_PL1_36") (pintype "bidirectional"))
    )
    (net (code "61") (name "D49") (class "Default")
      (node (ref "U6") (pin "35") (pinfunction "(ICP4)_PL0_35") (pintype "bidirectional"))
    )
    (net (code "62") (name "D54") (class "Default")
      (node (ref "U6") (pin "97") (pinfunction "PF0_(ADC0)_97") (pintype "bidirectional"))
    )
    (net (code "63") (name "D55") (class "Default")
      (node (ref "U6") (pin "96") (pinfunction "PF1_(ADC1)_96") (pintype "bidirectional"))
    )
    (net (code "64") (name "D56") (class "Default")
      (node (ref "U6") (pin "95") (pinfunction "PF2_(ADC2)_95") (pintype "bidirectional"))
    )
    (net (code "65") (name "D57") (class "Default")
      (node (ref "U6") (pin "94") (pinfunction "PF3_(ADC3)_94") (pintype "bidirectional"))
    )
    (net (code "66") (name "D58") (class "Default")
      (node (ref "MD_L") (pin "3") (pinfunction "3_3") (pintype "passive"))
      (node (ref "U6") (pin "93") (pinfunction "PF4_(ADC4/TCK)_93") (pintype "bidirectional"))
    )
    (net (code "67") (name "D59") (class "Default")
      (node (ref "U6") (pin "92") (pinfunction "PF5_(ADC5/TMS)_92") (pintype "bidirectional"))
    )
    (net (code "68") (name "D60") (class "Default")
      (node (ref "U6") (pin "91") (pinfunction "PF6_(ADC6/TDO)_91") (pintype "bidirectional"))
    )
    (net (code "69") (name "D67") (class "Default")
      (node (ref "U6") (pin "84") (pinfunction "PK5_(ADC13/PCINT21)_84") (pintype "input"))
    )
    (net (code "70") (name "D69") (class "Default")
      (node (ref "U6") (pin "82") (pinfunction "PK7_(ADC15/PCINT23)_82") (pintype "input"))
    )
    (net (code "71") (name "ESP_RX") (class "Default")
      (node (ref "ESP32") (pin "4") (pinfunction "4_4") (pintype "passive"))
      (node (ref "Q1") (pin "2") (pinfunction "S_2") (pintype "passive"))
      (node (ref "U$2") (pin "P$1") (pinfunction "P$1_P$1") (pintype "bidirectional"))
    )
    (net (code "72") (name "ESP_TX") (class "Default")
      (node (ref "ESP32") (pin "3") (pinfunction "3_3") (pintype "passive"))
      (node (ref "Q2") (pin "2") (pinfunction "S_2") (pintype "passive"))
      (node (ref "U$4") (pin "P$1") (pinfunction "P$1_P$1") (pintype "bidirectional"))
    )
    (net (code "73") (name "GND") (class "Default")
      (node (ref "+5V_IN") (pin "3") (pinfunction "3_3") (pintype "passive"))
      (node (ref "+5V_IN") (pin "4") (pinfunction "4_4") (pintype "passive"))
      (node (ref "328_RESET") (pin "3") (pinfunction "3_3") (pintype "bidirectional"))
      (node (ref "328_RESET") (pin "4") (pinfunction "4_4") (pintype "bidirectional"))
      (node (ref "ESP32") (pin "2") (pinfunction "2_2") (pintype "passive"))
      (node (ref "IR") (pin "2") (pinfunction "2_2") (pintype "passive"))
      (node (ref "J3") (pin "5") (pinfunction "5_5") (pintype "passive"))
      (node (ref "J3") (pin "S1") (pinfunction "SHIELD_S1") (pintype "passive"))
      (node (ref "J3") (pin "S2") (pinfunction "SHIELD_S2") (pintype "passive"))
      (node (ref "J3") (pin "S3") (pinfunction "SHIELD_S3") (pintype "passive"))
      (node (ref "J3") (pin "S4") (pinfunction "SHIELD_S4") (pintype "passive"))
      (node (ref "J3") (pin "S5") (pinfunction "SHIELD_S5") (pintype "passive"))
      (node (ref "J3") (pin "S6") (pinfunction "SHIELD_S6") (pintype "passive"))
      (node (ref "LINE") (pin "2") (pinfunction "2_2") (pintype "passive"))
      (node (ref "MD_L") (pin "2") (pinfunction "2_2") (pintype "passive"))
      (node (ref "MD_R") (pin "2") (pinfunction "2_2") (pintype "passive"))
      (node (ref "U$1") (pin "P$2") (pinfunction "P$2_P$2") (pintype "bidirectional"))
      (node (ref "U$10") (pin "P$1") (pinfunction "P$1_P$1") (pintype "bidirectional"))
      (node (ref "U$11") (pin "P$1") (pinfunction "P$1_P$1") (pintype "bidirectional"))
      (node (ref "U$117") (pin "P$1") (pinfunction "P$1_P$1") (pintype "bidirectional"))
      (node (ref "U$118") (pin "P$1") (pinfunction "P$1_P$1") (pintype "bidirectional"))
      (node (ref "U$119") (pin "P$1") (pinfunction "P$1_P$1") (pintype "bidirectional"))
      (node (ref "U$120") (pin "P$1") (pinfunction "P$1_P$1") (pintype "bidirectional"))
      (node (ref "U$121") (pin "P$1") (pinfunction "P$1_P$1") (pintype "bidirectional"))
      (node (ref "U$122") (pin "P$1") (pinfunction "P$1_P$1") (pintype "bidirectional"))
      (node (ref "U$13") (pin "GND") (pinfunction "GND_GND") (pintype "bidirectional"))
      (node (ref "U$13") (pin "GND2") (pinfunction "GND2_GND2") (pintype "bidirectional"))
      (node (ref "U$132") (pin "P$2") (pinfunction "2_P$2") (pintype "bidirectional"))
      (node (ref "U$133") (pin "P$2") (pinfunction "2_P$2") (pintype "bidirectional"))
      (node (ref "U$134") (pin "P$5") (pinfunction "P$5_P$5") (pintype "bidirectional"))
      (node (ref "U$137") (pin "-") (pinfunction "LED-_-") (pintype "bidirectional"))
      (node (ref "U$137") (pin "3") (pinfunction "3_3") (pintype "bidirectional"))
      (node (ref "U$137") (pin "4") (pinfunction "4_4") (pintype "bidirectional"))
      (node (ref "U$148") (pin "P$3") (pinfunction "P$2_P$3") (pintype "bidirectional"))
      (node (ref "U$149") (pin "P$2") (pinfunction "GND_P$2") (pintype "bidirectional"))
      (node (ref "U$150") (pin "P$2") (pinfunction "2_P$2") (pintype "bidirectional"))
      (node (ref "U$46") (pin "P$3") (pinfunction "P$3_P$3") (pintype "bidirectional"))
      (node (ref "U$6") (pin "P$1") (pinfunction "1_P$1") (pintype "bidirectional"))
      (node (ref "U$61") (pin "P$1") (pinfunction "1_P$1") (pintype "bidirectional"))
      (node (ref "U$7") (pin "P$2") (pinfunction "2_P$2") (pintype "bidirectional"))
      (node (ref "U$80") (pin "P$1") (pinfunction "P$1_P$1") (pintype "bidirectional"))
      (node (ref "U$80") (pin "P$4") (pinfunction "P$1_P$4") (pintype "bidirectional"))
      (node (ref "U$81") (pin "P$2") (pinfunction "2_P$2") (pintype "bidirectional"))
      (node (ref "U$82") (pin "P$2") (pinfunction "2_P$2") (pintype "bidirectional"))
      (node (ref "U$9") (pin "P$2") (pinfunction "1_P$2") (pintype "bidirectional"))
      (node (ref "U$93") (pin "P$2") (pinfunction "GND_P$2") (pintype "bidirectional"))
      (node (ref "U1") (pin "2") (pinfunction "GND_2") (pintype "power_in"))
      (node (ref "U2") (pin "21") (pinfunction "GND_21") (pintype "power_in"))
      (node (ref "U2") (pin "3") (pinfunction "GND_3") (pintype "power_in"))
      (node (ref "U2") (pin "5") (pinfunction "GND_5") (pintype "power_in"))
      (node (ref "U6") (pin "11") (pinfunction "GND_11") (pintype "power_in"))
      (node (ref "U6") (pin "32") (pinfunction "GND_32") (pintype "power_in"))
      (node (ref "U6") (pin "62") (pinfunction "GND_62") (pintype "power_in"))
      (node (ref "U6") (pin "81") (pinfunction "GND_81") (pintype "power_in"))
      (node (ref "U6") (pin "99") (pinfunction "GND_99") (pintype "power_in"))
      (node (ref "X2") (pin "2") (pinfunction "2_2") (pintype "passive"))
      (node (ref "X5") (pin "2") (pinfunction "2_2") (pintype "passive"))
      (node (ref "Y1") (pin "2") (pinfunction "GND_2") (pintype "power_in"))
      (node (ref "Y3") (pin "2") (pinfunction "GND_2") (pintype "power_in"))
    )
    (net (code "74") (name "LEVEL_RX") (class "Default")
      (node (ref "Q1") (pin "3") (pinfunction "D_3") (pintype "passive"))
      (node (ref "U$3") (pin "P$1") (pinfunction "P$1_P$1") (pintype "bidirectional"))
      (node (ref "U$8") (pin "P$1") (pinfunction "P$1_P$1") (pintype "bidirectional"))
    )
    (net (code "75") (name "LEVEL_TX") (class "Default")
      (node (ref "Q2") (pin "3") (pinfunction "D_3") (pintype "passive"))
      (node (ref "U$5") (pin "P$1") (pinfunction "P$1_P$1") (pintype "bidirectional"))
      (node (ref "U$8") (pin "P$6") (pinfunction "P$4_P$6") (pintype "bidirectional"))
    )
    (net (code "76") (name "MISO") (class "Default")
      (node (ref "U6") (pin "22") (pinfunction "(MISO/PCINT3)_PB3_22") (pintype "input"))
    )
    (net (code "77") (name "MOSI") (class "Default")
      (node (ref "U6") (pin "21") (pinfunction "(MOSI/PCINT2)_PB2_21") (pintype "input"))
    )
    (net (code "78") (name "Net-(D30-PadA)") (class "Default")
      (node (ref "D30") (pin "A") (pinfunction "A_A") (pintype "passive"))
      (node (ref "U$112") (pin "P$2") (pinfunction "P$2_P$2") (pintype "bidirectional"))
    )
    (net (code "79") (name "Net-(D31-PadA)") (class "Default")
      (node (ref "D31") (pin "A") (pinfunction "A_A") (pintype "passive"))
      (node (ref "U$113") (pin "P$2") (pinfunction "P$2_P$2") (pintype "bidirectional"))
    )
    (net (code "80") (name "Net-(D32-PadA)") (class "Default")
      (node (ref "D32") (pin "A") (pinfunction "A_A") (pintype "passive"))
      (node (ref "U$114") (pin "P$2") (pinfunction "P$2_P$2") (pintype "bidirectional"))
    )
    (net (code "81") (name "Net-(D33-PadA)") (class "Default")
      (node (ref "D33") (pin "A") (pinfunction "A_A") (pintype "passive"))
      (node (ref "U$115") (pin "P$2") (pinfunction "P$2_P$2") (pintype "bidirectional"))
    )
    (net (code "82") (name "Net-(J3-Pad2)") (class "Default")
      (node (ref "J3") (pin "2") (pinfunction "2_2") (pintype "passive"))
      (node (ref "U$46") (pin "P$2") (pinfunction "P$2_P$2") (pintype "bidirectional"))
    )
    (net (code "83") (name "Net-(J3-Pad3)") (class "Default")
      (node (ref "J3") (pin "3") (pinfunction "3_3") (pintype "passive"))
      (node (ref "U$46") (pin "P$1") (pinfunction "P$1_P$1") (pintype "bidirectional"))
    )
    (net (code "84") (name "Net-(JYRO-PadA)") (class "Default")
      (node (ref "JYRO") (pin "A") (pinfunction "A_A") (pintype "passive"))
      (node (ref "U$135") (pin "P$2") (pinfunction "P$2_P$2") (pintype "bidirectional"))
    )
    (net (code "85") (name "Net-(LED1-PadA)") (class "Default")
      (node (ref "LED1") (pin "A") (pinfunction "A_A") (pintype "passive"))
      (node (ref "U$109") (pin "P$1") (pinfunction "P$1_P$1") (pintype "bidirectional"))
    )
    (net (code "86") (name "Net-(LED3-PadA)") (class "Default")
      (node (ref "LED3") (pin "A") (pinfunction "A_A") (pintype "passive"))
      (node (ref "U$140") (pin "P$2") (pinfunction "P$2_P$2") (pintype "bidirectional"))
    )
    (net (code "87") (name "Net-(LED4-PadA)") (class "Default")
      (node (ref "LED4") (pin "A") (pinfunction "A_A") (pintype "passive"))
      (node (ref "U$141") (pin "P$2") (pinfunction "P$2_P$2") (pintype "bidirectional"))
    )
    (net (code "88") (name "Net-(LED5-PadA)") (class "Default")
      (node (ref "LED5") (pin "A") (pinfunction "A_A") (pintype "passive"))
      (node (ref "U$142") (pin "P$2") (pinfunction "P$2_P$2") (pintype "bidirectional"))
    )
    (net (code "89") (name "Net-(LED6-PadA)") (class "Default")
      (node (ref "LED6") (pin "A") (pinfunction "A_A") (pintype "passive"))
      (node (ref "U$143") (pin "P$2") (pinfunction "P$2_P$2") (pintype "bidirectional"))
    )
    (net (code "90") (name "Net-(LED7-PadA)") (class "Default")
      (node (ref "LED7") (pin "A") (pinfunction "A_A") (pintype "passive"))
      (node (ref "U$144") (pin "P$2") (pinfunction "P$2_P$2") (pintype "bidirectional"))
    )
    (net (code "91") (name "Net-(LED8-PadA)") (class "Default")
      (node (ref "LED8") (pin "A") (pinfunction "A_A") (pintype "passive"))
      (node (ref "U$145") (pin "P$2") (pinfunction "P$2_P$2") (pintype "bidirectional"))
    )
    (net (code "92") (name "Net-(LED9-PadA)") (class "Default")
      (node (ref "LED9") (pin "A") (pinfunction "A_A") (pintype "passive"))
      (node (ref "U$146") (pin "P$2") (pinfunction "P$2_P$2") (pintype "bidirectional"))
    )
    (net (code "93") (name "Net-(LED10-PadA)") (class "Default")
      (node (ref "LED10") (pin "A") (pinfunction "A_A") (pintype "passive"))
      (node (ref "U$147") (pin "P$2") (pinfunction "P$2_P$2") (pintype "bidirectional"))
    )
    (net (code "94") (name "Net-(LED11-PadA)") (class "Default")
      (node (ref "LED11") (pin "A") (pinfunction "A_A") (pintype "passive"))
      (node (ref "U$108") (pin "P$2") (pinfunction "P$2_P$2") (pintype "bidirectional"))
    )
    (net (code "95") (name "Net-(LED12-PadA)") (class "Default")
      (node (ref "LED12") (pin "A") (pinfunction "A_A") (pintype "passive"))
      (node (ref "U$111") (pin "P$1") (pinfunction "P$1_P$1") (pintype "bidirectional"))
    )
    (net (code "96") (name "Net-(LED13-PadA)") (class "Default")
      (node (ref "LED13") (pin "A") (pinfunction "A_A") (pintype "passive"))
      (node (ref "U$110") (pin "P$1") (pinfunction "P$1_P$1") (pintype "bidirectional"))
    )
    (net (code "97") (name "Net-(U$12-PadP$1)") (class "Default")
      (node (ref "U$12") (pin "P$1") (pinfunction "P$1_P$1") (pintype "bidirectional"))
      (node (ref "U$13") (pin "VO1") (pinfunction "VO1_VO1") (pintype "bidirectional"))
    )
    (net (code "98") (name "Net-(U$12-PadP$2)") (class "Default")
      (node (ref "U$12") (pin "P$2") (pinfunction "P$2_P$2") (pintype "bidirectional"))
      (node (ref "U$13") (pin "VO2") (pinfunction "VO2_VO2") (pintype "bidirectional"))
    )
    (net (code "99") (name "Net-(U$13-PadEN1)") (class "Default")
      (node (ref "U$13") (pin "EN1") (pinfunction "EN1_EN1") (pintype "bidirectional"))
      (node (ref "U$14") (pin "P$2") (pinfunction "P$2_P$2") (pintype "bidirectional"))
    )
    (net (code "100") (name "Net-(U$13-PadEN2)") (class "Default")
      (node (ref "U$13") (pin "EN2") (pinfunction "EN2_EN2") (pintype "bidirectional"))
      (node (ref "U$14") (pin "P$1") (pinfunction "P$1_P$1") (pintype "bidirectional"))
    )
    (net (code "101") (name "Net-(U$61-2)") (class "Default")
      (node (ref "U$46") (pin "P$10") (pinfunction "P$10_P$10") (pintype "bidirectional"))
      (node (ref "U$61") (pin "P$2") (pinfunction "2_P$2") (pintype "bidirectional"))
    )
    (net (code "102") (name "Net-(U$106-PadP$1)") (class "Default")
      (node (ref "U$106") (pin "P$1") (pinfunction "P$1_P$1") (pintype "bidirectional"))
      (node (ref "U$108") (pin "P$1") (pinfunction "P$1_P$1") (pintype "bidirectional"))
    )
    (net (code "103") (name "Net-(U$107-PadP$1)") (class "Default")
      (node (ref "U$107") (pin "P$1") (pinfunction "P$1_P$1") (pintype "bidirectional"))
      (node (ref "U$110") (pin "P$2") (pinfunction "P$2_P$2") (pintype "bidirectional"))
    )
    (net (code "104") (name "Net-(U$131-2)") (class "Default")
      (node (ref "U$131") (pin "P$2") (pinfunction "2_P$2") (pintype "bidirectional"))
      (node (ref "U$134") (pin "P$4") (pinfunction "P$4_P$4") (pintype "bidirectional"))
    )
    (net (code "105") (name "Net-(U$133-1)") (class "Default")
      (node (ref "U$133") (pin "P$1") (pinfunction "1_P$1") (pintype "bidirectional"))
      (node (ref "U2") (pin "20") (pinfunction "AREF_20") (pintype "input"))
    )
    (net (code "106") (name "Net-(U$134-PadP$2)") (class "Default")
      (node (ref "U$134") (pin "P$2") (pinfunction "P$2_P$2") (pintype "bidirectional"))
      (node (ref "U$136") (pin "P$1") (pinfunction "P$1_P$1") (pintype "bidirectional"))
    )
    (net (code "107") (name "Net-(U$136-P$4)") (class "Default")
      (node (ref "U$134") (pin "P$3") (pinfunction "P$3_P$3") (pintype "bidirectional"))
      (node (ref "U$136") (pin "P$6") (pinfunction "P$4_P$6") (pintype "bidirectional"))
    )
    (net (code "108") (name "Net-(U$137-LED+)") (class "Default")
      (node (ref "U$137") (pin "+") (pinfunction "LED+_+") (pintype "bidirectional"))
      (node (ref "U$138") (pin "P$2") (pinfunction "P$2_P$2") (pintype "bidirectional"))
    )
    (net (code "109") (name "Net-(U$148-P$3)") (class "Default")
      (node (ref "D30") (pin "K") (pinfunction "K_K") (pintype "passive"))
      (node (ref "D31") (pin "K") (pinfunction "K_K") (pintype "passive"))
      (node (ref "D32") (pin "K") (pinfunction "K_K") (pintype "passive"))
      (node (ref "D33") (pin "K") (pinfunction "K_K") (pintype "passive"))
      (node (ref "JYRO") (pin "K") (pinfunction "K_K") (pintype "passive"))
      (node (ref "LED1") (pin "K") (pinfunction "K_K") (pintype "passive"))
      (node (ref "LED10") (pin "K") (pinfunction "K_K") (pintype "passive"))
      (node (ref "LED11") (pin "K") (pinfunction "K_K") (pintype "passive"))
      (node (ref "LED12") (pin "K") (pinfunction "K_K") (pintype "passive"))
      (node (ref "LED13") (pin "K") (pinfunction "K_K") (pintype "passive"))
      (node (ref "LED3") (pin "K") (pinfunction "K_K") (pintype "passive"))
      (node (ref "LED4") (pin "K") (pinfunction "K_K") (pintype "passive"))
      (node (ref "LED5") (pin "K") (pinfunction "K_K") (pintype "passive"))
      (node (ref "LED6") (pin "K") (pinfunction "K_K") (pintype "passive"))
      (node (ref "LED7") (pin "K") (pinfunction "K_K") (pintype "passive"))
      (node (ref "LED8") (pin "K") (pinfunction "K_K") (pintype "passive"))
      (node (ref "LED9") (pin "K") (pinfunction "K_K") (pintype "passive"))
      (node (ref "U$148") (pin "P$2") (pinfunction "P$3_P$2") (pintype "bidirectional"))
    )
    (net (code "110") (name "Net-(U$150-1)") (class "Default")
      (node (ref "U$150") (pin "P$1") (pinfunction "1_P$1") (pintype "bidirectional"))
      (node (ref "U6") (pin "98") (pinfunction "AREF_98") (pintype "input"))
    )
    (net (code "111") (name "Net-(U$151-2)") (class "Default")
      (node (ref "U$151") (pin "P$2") (pinfunction "2_P$2") (pintype "bidirectional"))
      (node (ref "U$46") (pin "P$6") (pinfunction "P$6_P$6") (pintype "bidirectional"))
    )
    (net (code "112") (name "Net-(U2-PB6)") (class "Default")
      (node (ref "U2") (pin "7") (pinfunction "PB6_7") (pintype "bidirectional"))
      (node (ref "Y1") (pin "1") (pinfunction "IN_1") (pintype "input"))
    )
    (net (code "113") (name "Net-(U2-PB7)") (class "Default")
      (node (ref "U2") (pin "8") (pinfunction "PB7_8") (pintype "bidirectional"))
      (node (ref "Y1") (pin "3") (pinfunction "OUT_3") (pintype "output"))
    )
    (net (code "114") (name "Net-(U2-PD0)") (class "Default")
      (node (ref "U$136") (pin "P$5") (pinfunction "P$5_P$5") (pintype "bidirectional"))
      (node (ref "U2") (pin "30") (pinfunction "PD0_30") (pintype "bidirectional"))
    )
    (net (code "115") (name "Net-(U2-PD1)") (class "Default")
      (node (ref "U$136") (pin "P$2") (pinfunction "P$2_P$2") (pintype "bidirectional"))
      (node (ref "U2") (pin "31") (pinfunction "PD1_31") (pintype "bidirectional"))
    )
    (net (code "116") (name "RES") (class "Default")
      (node (ref "U$151") (pin "P$1") (pinfunction "1_P$1") (pintype "bidirectional"))
      (node (ref "U$79") (pin "P$1") (pinfunction "P$1_P$1") (pintype "bidirectional"))
      (node (ref "U$80") (pin "P$2") (pinfunction "P$2_P$2") (pintype "bidirectional"))
      (node (ref "U$80") (pin "P$3") (pinfunction "P$2_P$3") (pintype "bidirectional"))
      (node (ref "U6") (pin "30") (pinfunction "~{RESET}_30") (pintype "input"))
    )
    (net (code "117") (name "RX0") (class "Default")
      (node (ref "U$8") (pin "P$2") (pinfunction "P$2_P$2") (pintype "bidirectional"))
      (node (ref "U6") (pin "2") (pinfunction "(RXD0/PCINT8)_PE0_2") (pintype "input"))
    )
    (net (code "118") (name "RX1") (class "Default")
      (node (ref "LINE") (pin "3") (pinfunction "3_3") (pintype "passive"))
      (node (ref "U6") (pin "45") (pinfunction "(RXD1/INT2)_PD2_45") (pintype "input"))
    )
    (net (code "119") (name "RX2") (class "Default")
      (node (ref "U$136") (pin "P$3") (pinfunction "P$3_P$3") (pintype "bidirectional"))
      (node (ref "U6") (pin "12") (pinfunction "(RXD2)_PH0_12") (pintype "bidirectional"))
    )
    (net (code "120") (name "RX3") (class "Default")
      (node (ref "IR") (pin "3") (pinfunction "3_3") (pintype "passive"))
      (node (ref "U6") (pin "63") (pinfunction "PJ0_(RXD3/PCINT9)_63") (pintype "input"))
    )
    (net (code "121") (name "SCK") (class "Default")
      (node (ref "U6") (pin "20") (pinfunction "(SCK/PCINT1)_PB1_20") (pintype "input"))
    )
    (net (code "122") (name "SCL") (class "Default")
      (node (ref "U$149") (pin "P$9") (pinfunction "SCL_P$9") (pintype "bidirectional"))
      (node (ref "U6") (pin "43") (pinfunction "(SCL/INT0)_PD0_43") (pintype "input"))
    )
    (net (code "123") (name "SCL_328") (class "Default")
      (node (ref "U$93") (pin "P$3") (pinfunction "SCL_P$3") (pintype "bidirectional"))
      (node (ref "U2") (pin "28") (pinfunction "PC5_28") (pintype "bidirectional"))
    )
    (net (code "124") (name "SDA") (class "Default")
      (node (ref "U$149") (pin "P$10") (pinfunction "SDA_P$10") (pintype "bidirectional"))
      (node (ref "U6") (pin "44") (pinfunction "(SDA/INT1)_PD1_44") (pintype "input"))
    )
    (net (code "125") (name "SDA_328") (class "Default")
      (node (ref "U$93") (pin "P$4") (pinfunction "SDA_P$4") (pintype "bidirectional"))
      (node (ref "U2") (pin "27") (pinfunction "PC4_27") (pintype "bidirectional"))
    )
    (net (code "126") (name "SS") (class "Default")
      (node (ref "MD_R") (pin "3") (pinfunction "3_3") (pintype "passive"))
      (node (ref "U6") (pin "19") (pinfunction "(~{SS/PCINT0})_PB0_19") (pintype "input"))
    )
    (net (code "127") (name "TX0") (class "Default")
      (node (ref "U$8") (pin "P$5") (pinfunction "P$5_P$5") (pintype "bidirectional"))
      (node (ref "U6") (pin "3") (pinfunction "(TXD0)_PE1_3") (pintype "bidirectional"))
    )
    (net (code "128") (name "TX1") (class "Default")
      (node (ref "LINE") (pin "4") (pinfunction "4_4") (pintype "passive"))
      (node (ref "U6") (pin "46") (pinfunction "(TXD1/INT3)_PD3_46") (pintype "input"))
    )
    (net (code "129") (name "TX2") (class "Default")
      (node (ref "U$136") (pin "P$4") (pinfunction "P$6_P$4") (pintype "bidirectional"))
      (node (ref "U6") (pin "13") (pinfunction "(TXD2)_PH1_13") (pintype "bidirectional"))
    )
    (net (code "130") (name "TX3") (class "Default")
      (node (ref "IR") (pin "4") (pinfunction "4_4") (pintype "passive"))
      (node (ref "U6") (pin "64") (pinfunction "PJ1_(TXD3/PCINT10)_64") (pintype "input"))
    )
    (net (code "131") (name "USB_RX") (class "Default")
      (node (ref "U$46") (pin "P$8") (pinfunction "P$8_P$8") (pintype "bidirectional"))
      (node (ref "U$8") (pin "P$3") (pinfunction "P$3_P$3") (pintype "bidirectional"))
    )
    (net (code "132") (name "USB_TX") (class "Default")
      (node (ref "U$46") (pin "P$9") (pinfunction "P$9_P$9") (pintype "bidirectional"))
      (node (ref "U$8") (pin "P$4") (pinfunction "P$6_P$4") (pintype "bidirectional"))
    )
    (net (code "133") (name "XT1") (class "Default")
      (node (ref "U6") (pin "34") (pinfunction "XTAL1_34") (pintype "input"))
      (node (ref "Y3") (pin "1") (pinfunction "IN_1") (pintype "input"))
    )
    (net (code "134") (name "XT2") (class "Default")
      (node (ref "U6") (pin "33") (pinfunction "XTAL2_33") (pintype "output"))
      (node (ref "Y3") (pin "3") (pinfunction "OUT_3") (pintype "output"))
    )
    (net (code "135") (name "unconnected-(ESP32-Pad5)") (class "Default")
      (node (ref "ESP32") (pin "5") (pinfunction "5_5") (pintype "passive"))
    )
    (net (code "136") (name "unconnected-(J3-Pad4)") (class "Default")
      (node (ref "J3") (pin "4") (pinfunction "4_4") (pintype "passive"))
    )
    (net (code "137") (name "unconnected-(MD_L-Pad4)") (class "Default")
      (node (ref "MD_L") (pin "4") (pinfunction "4_4") (pintype "passive"))
    )
    (net (code "138") (name "unconnected-(MD_R-Pad4)") (class "Default")
      (node (ref "MD_R") (pin "4") (pinfunction "4_4") (pintype "passive"))
    )
    (net (code "139") (name "unconnected-(U$9-3-PadP$4)") (class "Default")
      (node (ref "U$9") (pin "P$4") (pinfunction "3_P$4") (pintype "bidirectional"))
    )
    (net (code "140") (name "unconnected-(U$46-PadP$4)") (class "Default")
      (node (ref "U$46") (pin "P$4") (pinfunction "P$4_P$4") (pintype "bidirectional"))
    )
    (net (code "141") (name "unconnected-(U$46-PadP$5)") (class "Default")
      (node (ref "U$46") (pin "P$5") (pinfunction "P$5_P$5") (pintype "bidirectional"))
    )
    (net (code "142") (name "unconnected-(U$93-ADO-PadP$7)") (class "Default")
      (node (ref "U$93") (pin "P$7") (pinfunction "ADO_P$7") (pintype "bidirectional"))
    )
    (net (code "143") (name "unconnected-(U$93-INT-PadP$8)") (class "Default")
      (node (ref "U$93") (pin "P$8") (pinfunction "INT_P$8") (pintype "bidirectional"))
    )
    (net (code "144") (name "unconnected-(U$93-XCL-PadP$6)") (class "Default")
      (node (ref "U$93") (pin "P$6") (pinfunction "XCL_P$6") (pintype "bidirectional"))
    )
    (net (code "145") (name "unconnected-(U$93-XDA-PadP$5)") (class "Default")
      (node (ref "U$93") (pin "P$5") (pinfunction "XDA_P$5") (pintype "bidirectional"))
    )
    (net (code "146") (name "unconnected-(U$148-PadP$1)") (class "Default")
      (node (ref "U$148") (pin "P$1") (pinfunction "P$1_P$1") (pintype "bidirectional"))
    )
    (net (code "147") (name "unconnected-(U2-ADC6-Pad19)") (class "Default")
      (node (ref "U2") (pin "19") (pinfunction "ADC6_19") (pintype "bidirectional"))
    )
    (net (code "148") (name "unconnected-(U2-ADC7-Pad22)") (class "Default")
      (node (ref "U2") (pin "22") (pinfunction "ADC7_22") (pintype "bidirectional"))
    )
    (net (code "149") (name "unconnected-(U2-PC0-Pad23)") (class "Default")
      (node (ref "U2") (pin "23") (pinfunction "PC0_23") (pintype "bidirectional"))
    )
    (net (code "150") (name "unconnected-(U2-PC1-Pad24)") (class "Default")
      (node (ref "U2") (pin "24") (pinfunction "PC1_24") (pintype "bidirectional"))
    )
    (net (code "151") (name "unconnected-(U2-PC2-Pad25)") (class "Default")
      (node (ref "U2") (pin "25") (pinfunction "PC2_25") (pintype "bidirectional"))
    )
    (net (code "152") (name "unconnected-(U2-PC3-Pad26)") (class "Default")
      (node (ref "U2") (pin "26") (pinfunction "PC3_26") (pintype "bidirectional"))
    )
    (net (code "153") (name "unconnected-(U6-(CLKO{slash}ICP3{slash}INT7)_PE7-Pad9)") (class "Default")
      (node (ref "U6") (pin "9") (pinfunction "(CLKO/ICP3/INT7)_PE7_9") (pintype "input"))
    )
    (net (code "154") (name "unconnected-(U6-(ICP1)_PD4-Pad47)") (class "Default")
      (node (ref "U6") (pin "47") (pinfunction "(ICP1)_PD4_47") (pintype "bidirectional"))
    )
    (net (code "155") (name "unconnected-(U6-(T1)_PD6-Pad49)") (class "Default")
      (node (ref "U6") (pin "49") (pinfunction "(T1)_PD6_49") (pintype "bidirectional"))
    )
    (net (code "156") (name "unconnected-(U6-(T3{slash}INT6)_PE6-Pad8)") (class "Default")
      (node (ref "U6") (pin "8") (pinfunction "(T3/INT6)_PE6_8") (pintype "input"))
    )
    (net (code "157") (name "unconnected-(U6-(T4)_PH7-Pad27)") (class "Default")
      (node (ref "U6") (pin "27") (pinfunction "(T4)_PH7_27") (pintype "bidirectional"))
    )
    (net (code "158") (name "unconnected-(U6-(TOSC1)_PG4-Pad29)") (class "Default")
      (node (ref "U6") (pin "29") (pinfunction "(TOSC1)_PG4_29") (pintype "bidirectional"))
    )
    (net (code "159") (name "unconnected-(U6-(TOSC2)_PG3-Pad28)") (class "Default")
      (node (ref "U6") (pin "28") (pinfunction "(TOSC2)_PG3_28") (pintype "bidirectional"))
    )
    (net (code "160") (name "unconnected-(U6-(XCK0{slash}AIN0)_PE2-Pad4)") (class "Default")
      (node (ref "U6") (pin "4") (pinfunction "(XCK0/AIN0)_PE2_4") (pintype "input"))
    )
    (net (code "161") (name "unconnected-(U6-(XCK1)_PD5-Pad48)") (class "Default")
      (node (ref "U6") (pin "48") (pinfunction "(XCK1)_PD5_48") (pintype "bidirectional"))
    )
    (net (code "162") (name "unconnected-(U6-(XCK2)_PH2-Pad14)") (class "Default")
      (node (ref "U6") (pin "14") (pinfunction "(XCK2)_PH2_14") (pintype "bidirectional"))
    )
    (net (code "163") (name "unconnected-(U6-PJ2_(XCK3{slash}PCINT11)-Pad65)") (class "Default")
      (node (ref "U6") (pin "65") (pinfunction "PJ2_(XCK3/PCINT11)_65") (pintype "input"))
    )
    (net (code "164") (name "unconnected-(U6-PJ3_(PCINT12)-Pad66)") (class "Default")
      (node (ref "U6") (pin "66") (pinfunction "PJ3_(PCINT12)_66") (pintype "input"))
    )
    (net (code "165") (name "unconnected-(U6-PJ4_(PCINT13)-Pad67)") (class "Default")
      (node (ref "U6") (pin "67") (pinfunction "PJ4_(PCINT13)_67") (pintype "input"))
    )
    (net (code "166") (name "unconnected-(U6-PJ5_(PCINT14)-Pad68)") (class "Default")
      (node (ref "U6") (pin "68") (pinfunction "PJ5_(PCINT14)_68") (pintype "input"))
    )
    (net (code "167") (name "unconnected-(U6-PJ6_(PCINT15)-Pad69)") (class "Default")
      (node (ref "U6") (pin "69") (pinfunction "PJ6_(PCINT15)_69") (pintype "input"))
    )
    (net (code "168") (name "unconnected-(U6-PJ7-Pad79)") (class "Default")
      (node (ref "U6") (pin "79") (pinfunction "PJ7_79") (pintype "bidirectional"))
    )
    (net (code "169") (name "unconnected-(X2-Pad1)") (class "Default")
      (node (ref "X2") (pin "1") (pinfunction "1_1") (pintype "passive"))
    )
  )
)
